# MCU.net
KiCad netlist of a schematic drawn in Altium Designer
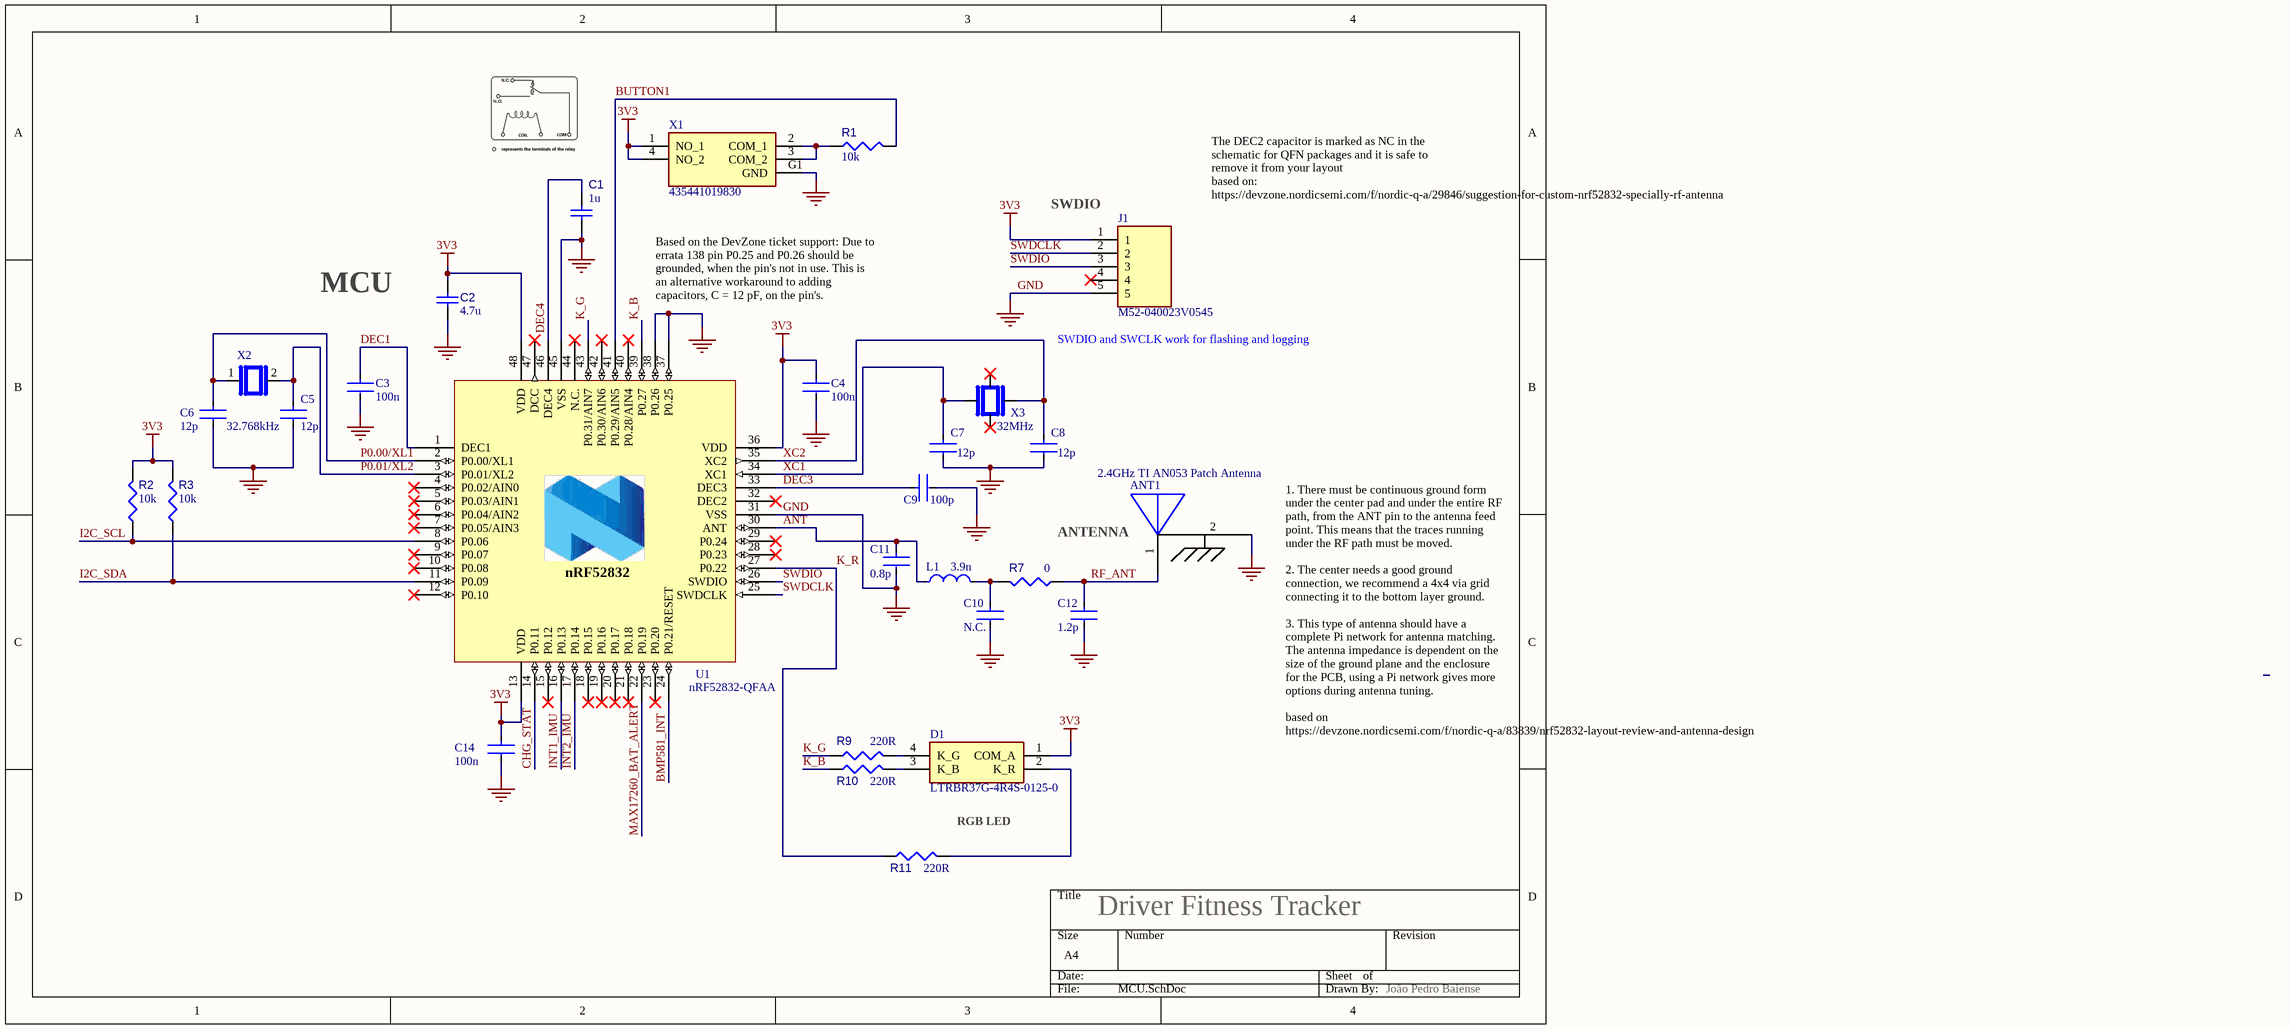
[diagram p0: MCU.SchDoc]

(export (version "E")
  (design (tool "Eeschema 10.0.6"))
  (components
    (comp (ref "ANT1")
      (value "2.4GHz TI AN053 Patch Antenna")
      (footprint "2.4GHz TI AN053 Patch Antenna Right Original")
      (description "From Application Note AN053")
      (libsource (lib "Tese_SymbolLib") (part "2.4GHz Antenna with GND"))
    )
    (comp (ref "C1")
      (value "1u")
      (footprint "CAPC1608X90X40NL10T20")
      (description "Multilayer Ceramic Capacitors MLCC - SMD/SMT 50V 1uF X7R 0603 10%")
      (fields (field (name "TOLERANCE") "10%") (field (name "JLCPCB PART #") "C15849"))
      (libsource (lib "Tese_project") (part "CAP-NP-2"))
    )
    (comp (ref "C2")
      (value "4.7u")
      (footprint "CAPC1608X90X40NL10T20")
      (description "Chip Capacitor, 100 nF, +/- 10%, 50 V, 0603 (1608 Metric)")
      (fields (field (name "TOLERANCE") "10%") (field (name "JLCPCB PART #") "C14663"))
      (libsource (lib "Tese_project") (part "CAP-NP-2"))
    )
    (comp (ref "C3")
      (value "100n")
      (footprint "FP-C0402-BB-MFG")
      (description "Multilayer Ceramic Capacitors MLCC - SMD/SMT NEW GLOBAL PN KGM05CR71H104KN 50V 0.1uF X7R 0402 10%")
      (fields (field (name "MANUFACTURER") "Kemet") (field (name "TOLERANCE") "0.1"))
      (libsource (lib "Altium Content Vault") (part "b4654b650e69147ec39a6b967a45e02"))
    )
    (comp (ref "C4")
      (value "100n")
      (footprint "FP-C0402-BB-MFG")
      (description "Multilayer Ceramic Capacitors MLCC - SMD/SMT NEW GLOBAL PN KGM05CR71H104KN 50V 0.1uF X7R 0402 10%")
      (fields (field (name "MANUFACTURER") "Kemet") (field (name "TOLERANCE") "0.1"))
      (libsource (lib "Altium Content Vault") (part "b4654b650e69147ec39a6b967a45e02"))
    )
    (comp (ref "C5")
      (value "12p")
      (footprint "FP-C0402-BB-MFG")
      (description "Multilayer Ceramic Capacitors MLCC - SMD/SMT 12 pF 50 VDC 5% 0402 C0G (NP0)")
      (fields (field (name "MANUFACTURER") "Kemet") (field (name "TOLERANCE") "0.1"))
      (libsource (lib "Altium Content Vault") (part "b4654b650e69147ec39a6b967a45e02"))
    )
    (comp (ref "C6")
      (value "12p")
      (footprint "FP-C0402-BB-MFG")
      (description "Multilayer Ceramic Capacitors MLCC - SMD/SMT 12 pF 50 VDC 5% 0402 C0G (NP0)")
      (fields (field (name "MANUFACTURER") "Kemet") (field (name "TOLERANCE") "0.1"))
      (libsource (lib "Altium Content Vault") (part "b4654b650e69147ec39a6b967a45e02"))
    )
    (comp (ref "C7")
      (value "12p")
      (footprint "FP-C0402-BB-MFG")
      (description "Multilayer Ceramic Capacitors MLCC - SMD/SMT 12 pF 50 VDC 5% 0402 C0G (NP0)")
      (fields (field (name "MANUFACTURER") "Kemet") (field (name "TOLERANCE") "0.1"))
      (libsource (lib "Altium Content Vault") (part "b4654b650e69147ec39a6b967a45e02"))
    )
    (comp (ref "C8")
      (value "12p")
      (footprint "FP-C0402-BB-MFG")
      (description "Multilayer Ceramic Capacitors MLCC - SMD/SMT 12 pF 50 VDC 5% 0402 C0G (NP0)")
      (fields (field (name "MANUFACTURER") "Kemet") (field (name "TOLERANCE") "0.1"))
      (libsource (lib "Altium Content Vault") (part "b4654b650e69147ec39a6b967a45e02"))
    )
    (comp (ref "C9")
      (value "100p")
      (footprint "FP-C0402-BB-MFG")
      (description "Multilayer Ceramic Capacitors MLCC - SMD/SMT 100 pF 50 VDC 5% 0402 C0G (NP0)")
      (fields (field (name "MANUFACTURER") "Kemet") (field (name "TOLERANCE") "0.1"))
      (libsource (lib "Altium Content Vault") (part "b4654b650e69147ec39a6b967a45e02"))
    )
    (comp (ref "C10")
      (value "N.C.")
      (footprint "FP-C0402-BB-MFG")
      (description "DO NOT CONNECT THIS CAPACITOR - RF PURPOSE")
      (libsource (lib "Altium Content Vault") (part "b4654b650e69147ec39a6b967a45e02"))
    )
    (comp (ref "C11")
      (value "0.8p")
      (footprint "FP-C0402-BB-MFG")
      (description "Multilayer Ceramic Capacitors MLCC - SMD/SMT 0.8 pF 50 VDC 0.05 pF 0402 C0G (NP0) AEC-Q200")
      (fields (field (name "MANUFACTURER") "Murata Electronics") (field (name "TOLERANCE") "0.1"))
      (libsource (lib "Altium Content Vault") (part "b4654b650e69147ec39a6b967a45e02"))
    )
    (comp (ref "C12")
      (value "1.2p")
      (footprint "FP-C0402-BB-MFG")
      (fields
        (field (name "MANUFACTURER") "Kemet")
        (field (name "TOLERANCE") "0.1")
        (field (name "OCTOPART") "https://octopart.com/c0402c104k8pactu-kemet-140039")
      )
      (libsource (lib "Altium Content Vault") (part "b4654b650e69147ec39a6b967a45e02"))
    )
    (comp (ref "C14")
      (value "100n")
      (footprint "FP-C0402-BB-MFG")
      (description "Multilayer Ceramic Capacitors MLCC - SMD/SMT NEW GLOBAL PN KGM05CR71H104KN 50V 0.1uF X7R 0402 10%")
      (fields (field (name "MANUFACTURER") "Kemet") (field (name "TOLERANCE") "0.1"))
      (libsource (lib "Altium Content Vault") (part "b4654b650e69147ec39a6b967a45e02"))
    )
    (comp (ref "D1")
      (value "LTRBR37G-4R4S-0125-0")
      (footprint "RGBLED_LTRBR37G4R4S01250")
      (description "Standard LEDs - SMD LTRBR37G")
      (fields (field (name "MOUSER PART NUMBER") "720-LTRBR37GA6714"))
      (libsource (lib "Tese_SymbolLib") (part "RGBLED_LTRBR37G-4R4S-0125-0"))
    )
    (comp (ref "J1")
      (value "M52-040023V0545")
      (footprint "5_PINS_HEADER_HDRV5W46P0X127_1X5_635X250X650P")
      (description "Headers & Wire Housings Pin1.27mm Tail,Vert SIL, 5P, Single Row")
      (fields (field (name "MOUSER PART NUMBER") "855-M52-040023V0545"))
      (libsource (lib "Tese_SymbolLib") (part "5_PINS_HEADER_M52-040023V0545"))
    )
    (comp (ref "L1")
      (value "3.9n")
      (footprint "FP-LQW15AN_00-W0_6-0_1-MFG")
      (description "RF Inductors - SMD 01005, 3.9nH +-0.2nH S-HQ SMD RF IND")
      (fields (field (name "JLCPCB PART #") "C14033"))
      (libsource (lib "Altium Content Vault") (part "725321dda6339637d4d059423bc1c3c"))
    )
    (comp (ref "R1")
      (value "10k")
      (footprint "RESC0402(1005)_L")
      (description "Thin Film Resistors - SMD 1/16W 10K ohm 1% 50ppm")
      (fields (field (name "POWER") "63mW") (field (name "TOLERANCE") "1%"))
      (libsource (lib "Tese_project") (part "RES-2"))
    )
    (comp (ref "R2")
      (value "10k")
      (footprint "RESC0402(1005)_L")
      (description "Thin Film Resistors - SMD 1/16W 10K ohm 1% 50ppm")
      (fields (field (name "POWER") "63mW") (field (name "TOLERANCE") "1%"))
      (libsource (lib "Tese_project") (part "RES-2"))
    )
    (comp (ref "R3")
      (value "10k")
      (footprint "RESC0402(1005)_L")
      (description "Thin Film Resistors - SMD 1/16W 10K ohm 1% 50ppm")
      (fields (field (name "POWER") "63mW") (field (name "TOLERANCE") "1%"))
      (libsource (lib "Tese_project") (part "RES-2"))
    )
    (comp (ref "R7")
      (value "0")
      (footprint "RESC0402(1005)_L")
      (description "Thin Film Resistors - SMD MCS 0402 VG01 E1 0R0")
      (fields (field (name "POWER") "63mW") (field (name "TOLERANCE") "1%"))
      (libsource (lib "Tese_project") (part "RES-2"))
    )
    (comp (ref "R9")
      (value "220R")
      (footprint "RESC0402(1005)_L")
      (description "Thin Film Resistors - SMD .063W 220ohms 1% 0402 50ppm")
      (fields (field (name "POWER") "63mW") (field (name "TOLERANCE") "1%"))
      (libsource (lib "Tese_project") (part "RES-2"))
    )
    (comp (ref "R10")
      (value "220R")
      (footprint "RESC0402(1005)_L")
      (description "Thin Film Resistors - SMD .063W 220ohms 1% 0402 50ppm")
      (fields (field (name "POWER") "63mW") (field (name "TOLERANCE") "1%"))
      (libsource (lib "Tese_project") (part "RES-2"))
    )
    (comp (ref "R11")
      (value "220R")
      (footprint "RESC0402(1005)_L")
      (description "Thin Film Resistors - SMD .063W 220ohms 1% 0402 50ppm")
      (fields (field (name "POWER") "63mW") (field (name "TOLERANCE") "1%"))
      (libsource (lib "Tese_project") (part "RES-2"))
    )
    (comp (ref "U1")
      (value "nRF52832-QFAA")
      (footprint "QFN40P600X600X90-48N")
      (description "Multi-protocol Bluetooth Low Energy, ANT and 2.4GHz proprietary system-on-chip")
      (fields
        (field (name "MANUFACTURER") "Nordic Semiconductor")
        (field (name "JLCPCB PART #") "C77540")
        (field (name "PUBLISHER") "Nordic Semiconductor")
      )
      (libsource (lib "Tese_SymbolLib") (part "nRF52832_QFAA"))
    )
    (comp (ref "X1")
      (value "435441019830")
      (footprint "BUTTON_435441019830")
      (description "Tactile Switches WS-TASV Tact Switch Washable 4.1x2.8x1.9 mm SMT")
      (fields (field (name "MOUSER PART NUMBER") "710-435441019830"))
      (libsource (lib "Tese_SymbolLib") (part "BUTTON_435441019830"))
    )
    (comp (ref "X2")
      (value "32.768kHz")
      (footprint "CRYSTAL_XTAL_CM8V-T1A-32.768KHZ-9PF-20PPM-TA-QC")
      (description "Crystals 32.768 kHz 9.0 pF +/-20 PPM -40/+85C")
      (fields (field (name "MF") "Micro Crystal"))
      (libsource (lib "Tese_SymbolLib") (part "CRYSTAL_32K"))
    )
    (comp (ref "X3")
      (value "32MHz")
      (footprint "OSC_XRCGB32M000F1H01R0")
      (description "Crystals 32 MHZ 10PPM 2.0X1.6X")
      (fields (field (name "MF") "Murata Electronics") (field (name "JLCPCB PART #") "C914155"))
      (libsource (lib "Tese_SymbolLib") (part "XRCGB32M000F1H01R0"))
    )
  )
  (nets
    (net (code "1") (name "/ANT") (class "Default")
      (node (ref "C11") (pin "1") (pinfunction "1_1") (pintype "passive"))
      (node (ref "L1") (pin "1") (pinfunction "1_1") (pintype "passive"))
      (node (ref "U1") (pin "30") (pinfunction "ANT_30") (pintype "bidirectional"))
    )
    (net (code "2") (name "/BMP581_INT") (class "Default")
      (node (ref "U1") (pin "24") (pinfunction "P0.21/RESET_24") (pintype "bidirectional"))
    )
    (net (code "3") (name "/BUTTON1") (class "Default")
      (node (ref "R1") (pin "2") (pinfunction "2_2") (pintype "passive"))
      (node (ref "U1") (pin "41") (pinfunction "P0.29/AIN5_41") (pintype "bidirectional"))
    )
    (net (code "4") (name "/CHG_STAT") (class "Default")
      (node (ref "U1") (pin "14") (pinfunction "P0.11_14") (pintype "bidirectional"))
    )
    (net (code "5") (name "/DEC1") (class "Default")
      (node (ref "C3") (pin "1") (pinfunction "1_1") (pintype "passive"))
      (node (ref "U1") (pin "1") (pinfunction "DEC1_1") (pintype "power_in"))
    )
    (net (code "6") (name "/DEC3") (class "Default")
      (node (ref "C9") (pin "1") (pinfunction "1_1") (pintype "passive"))
      (node (ref "U1") (pin "33") (pinfunction "DEC3_33") (pintype "power_in"))
    )
    (net (code "7") (name "/DEC4") (class "Default")
      (node (ref "C1") (pin "1") (pinfunction "1_1") (pintype "passive"))
      (node (ref "U1") (pin "46") (pinfunction "DEC4_46") (pintype "power_in"))
    )
    (net (code "8") (name "/I2C_SCL") (class "Default")
      (node (ref "R2") (pin "1") (pinfunction "1_1") (pintype "passive"))
      (node (ref "U1") (pin "8") (pinfunction "P0.06_8") (pintype "bidirectional"))
    )
    (net (code "9") (name "/I2C_SDA") (class "Default")
      (node (ref "R3") (pin "1") (pinfunction "1_1") (pintype "passive"))
      (node (ref "U1") (pin "11") (pinfunction "P0.09_11") (pintype "bidirectional"))
    )
    (net (code "10") (name "/INT1_IMU") (class "Default")
      (node (ref "U1") (pin "16") (pinfunction "P0.13_16") (pintype "bidirectional"))
    )
    (net (code "11") (name "/INT2_IMU") (class "Default")
      (node (ref "U1") (pin "17") (pinfunction "P0.14_17") (pintype "bidirectional"))
    )
    (net (code "12") (name "/K_B") (class "Default")
      (node (ref "R10") (pin "1") (pinfunction "1_1") (pintype "passive"))
      (node (ref "U1") (pin "39") (pinfunction "P0.27_39") (pintype "bidirectional"))
    )
    (net (code "13") (name "/K_G") (class "Default")
      (node (ref "R9") (pin "1") (pinfunction "1_1") (pintype "passive"))
      (node (ref "U1") (pin "43") (pinfunction "P0.31/AIN7_43") (pintype "bidirectional"))
    )
    (net (code "14") (name "/K_R") (class "Default")
      (node (ref "R11") (pin "1") (pinfunction "1_1") (pintype "passive"))
      (node (ref "U1") (pin "27") (pinfunction "P0.22_27") (pintype "bidirectional"))
    )
    (net (code "15") (name "/MAX17260_BAT_ALERT") (class "Default")
      (node (ref "U1") (pin "22") (pinfunction "P0.19_22") (pintype "bidirectional"))
    )
    (net (code "16") (name "/P0.00{slash}XL1") (class "Default")
      (node (ref "C6") (pin "1") (pinfunction "1_1") (pintype "passive"))
      (node (ref "U1") (pin "2") (pinfunction "P0.00/XL1_2") (pintype "bidirectional"))
      (node (ref "X2") (pin "1") (pinfunction "1_1") (pintype "passive"))
    )
    (net (code "17") (name "/P0.01{slash}XL2") (class "Default")
      (node (ref "C5") (pin "1") (pinfunction "1_1") (pintype "passive"))
      (node (ref "U1") (pin "3") (pinfunction "P0.01/XL2_3") (pintype "bidirectional"))
      (node (ref "X2") (pin "2") (pinfunction "2_2") (pintype "passive"))
    )
    (net (code "18") (name "/RF_ANT") (class "Default")
      (node (ref "ANT1") (pin "1") (pinfunction "ANT_1") (pintype "passive"))
      (node (ref "C12") (pin "1") (pinfunction "1_1") (pintype "passive"))
      (node (ref "R7") (pin "1") (pinfunction "1_1") (pintype "passive"))
    )
    (net (code "19") (name "/SWDCLK") (class "Default")
      (node (ref "J1") (pin "2") (pinfunction "2_2") (pintype "passive"))
      (node (ref "U1") (pin "25") (pinfunction "SWDCLK_25") (pintype "input"))
    )
    (net (code "20") (name "/SWDIO") (class "Default")
      (node (ref "J1") (pin "3") (pinfunction "3_3") (pintype "passive"))
      (node (ref "U1") (pin "26") (pinfunction "SWDIO_26") (pintype "bidirectional"))
    )
    (net (code "21") (name "/XC1") (class "Default")
      (node (ref "C7") (pin "1") (pinfunction "1_1") (pintype "passive"))
      (node (ref "U1") (pin "34") (pinfunction "XC1_34") (pintype "input"))
      (node (ref "X3") (pin "1") (pinfunction "1_1") (pintype "passive"))
    )
    (net (code "22") (name "/XC2") (class "Default")
      (node (ref "C8") (pin "1") (pinfunction "1_1") (pintype "passive"))
      (node (ref "U1") (pin "35") (pinfunction "XC2_35") (pintype "output"))
      (node (ref "X3") (pin "3") (pinfunction "3_3") (pintype "passive"))
    )
    (net (code "23") (name "3V3") (class "Default")
      (node (ref "C14") (pin "1") (pinfunction "1_1") (pintype "passive"))
      (node (ref "C2") (pin "1") (pinfunction "1_1") (pintype "passive"))
      (node (ref "C4") (pin "1") (pinfunction "1_1") (pintype "passive"))
      (node (ref "D1") (pin "1") (pinfunction "COM_A_1") (pintype "passive"))
      (node (ref "J1") (pin "1") (pinfunction "1_1") (pintype "passive"))
      (node (ref "R2") (pin "2") (pinfunction "2_2") (pintype "passive"))
      (node (ref "R3") (pin "2") (pinfunction "2_2") (pintype "passive"))
      (node (ref "U1") (pin "13") (pinfunction "VDD_13") (pintype "power_in"))
      (node (ref "U1") (pin "36") (pinfunction "VDD_36") (pintype "power_in"))
      (node (ref "U1") (pin "48") (pinfunction "VDD_48") (pintype "power_in"))
      (node (ref "X1") (pin "1") (pinfunction "NO_1_1") (pintype "passive"))
      (node (ref "X1") (pin "4") (pinfunction "NO_2_4") (pintype "passive"))
    )
    (net (code "24") (name "GND") (class "Default")
      (node (ref "ANT1") (pin "2") (pintype "passive"))
      (node (ref "C1") (pin "2") (pinfunction "2_2") (pintype "passive"))
      (node (ref "C10") (pin "2") (pinfunction "2_2") (pintype "passive"))
      (node (ref "C11") (pin "2") (pinfunction "2_2") (pintype "passive"))
      (node (ref "C12") (pin "2") (pinfunction "2_2") (pintype "passive"))
      (node (ref "C14") (pin "2") (pinfunction "2_2") (pintype "passive"))
      (node (ref "C2") (pin "2") (pinfunction "2_2") (pintype "passive"))
      (node (ref "C3") (pin "2") (pinfunction "2_2") (pintype "passive"))
      (node (ref "C4") (pin "2") (pinfunction "2_2") (pintype "passive"))
      (node (ref "C5") (pin "2") (pinfunction "2_2") (pintype "passive"))
      (node (ref "C6") (pin "2") (pinfunction "2_2") (pintype "passive"))
      (node (ref "C7") (pin "2") (pinfunction "2_2") (pintype "passive"))
      (node (ref "C8") (pin "2") (pinfunction "2_2") (pintype "passive"))
      (node (ref "C9") (pin "2") (pinfunction "2_2") (pintype "passive"))
      (node (ref "J1") (pin "5") (pinfunction "5_5") (pintype "passive"))
      (node (ref "U1") (pin "31") (pinfunction "VSS_31") (pintype "power_in"))
      (node (ref "U1") (pin "37") (pinfunction "P0.25_37") (pintype "bidirectional"))
      (node (ref "U1") (pin "38") (pinfunction "P0.26_38") (pintype "bidirectional"))
      (node (ref "U1") (pin "45") (pinfunction "VSS_45") (pintype "power_in"))
      (node (ref "U1") (pin "49") (pinfunction "GND_49") (pintype "power_in"))
      (node (ref "X1") (pin "G1") (pinfunction "GND_G1") (pintype "passive"))
    )
    (net (code "25") (name "Net-(C10-Pad1)") (class "Default")
      (node (ref "C10") (pin "1") (pinfunction "1_1") (pintype "passive"))
      (node (ref "L1") (pin "2") (pinfunction "2_2") (pintype "passive"))
      (node (ref "R7") (pin "2") (pinfunction "2_2") (pintype "passive"))
    )
    (net (code "26") (name "Net-(D1-K_B)") (class "Default")
      (node (ref "D1") (pin "3") (pinfunction "K_B_3") (pintype "passive"))
      (node (ref "R10") (pin "2") (pinfunction "2_2") (pintype "passive"))
    )
    (net (code "27") (name "Net-(D1-K_G)") (class "Default")
      (node (ref "D1") (pin "4") (pinfunction "K_G_4") (pintype "passive"))
      (node (ref "R9") (pin "2") (pinfunction "2_2") (pintype "passive"))
    )
    (net (code "28") (name "Net-(D1-K_R)") (class "Default")
      (node (ref "D1") (pin "2") (pinfunction "K_R_2") (pintype "passive"))
      (node (ref "R11") (pin "2") (pinfunction "2_2") (pintype "passive"))
    )
    (net (code "29") (name "Net-(X1-COM_1)") (class "Default")
      (node (ref "R1") (pin "1") (pinfunction "1_1") (pintype "passive"))
      (node (ref "X1") (pin "2") (pinfunction "COM_1_2") (pintype "passive"))
      (node (ref "X1") (pin "3") (pinfunction "COM_2_3") (pintype "passive"))
    )
    (net (code "30") (name "unconnected-(J1-Pad4)") (class "Default")
      (node (ref "J1") (pin "4") (pinfunction "4_4") (pintype "passive+no_connect"))
    )
    (net (code "31") (name "unconnected-(U1-DCC-Pad47)") (class "Default")
      (node (ref "U1") (pin "47") (pinfunction "DCC_47") (pintype "output+no_connect"))
    )
    (net (code "32") (name "unconnected-(U1-DEC2-Pad32)") (class "Default")
      (node (ref "U1") (pin "32") (pinfunction "DEC2_32") (pintype "power_in+no_connect"))
    )
    (net (code "33") (name "unconnected-(U1-N.C.-Pad44)") (class "Default")
      (node (ref "U1") (pin "44") (pinfunction "N.C._44") (pintype "power_in+no_connect"))
    )
    (net (code "34") (name "unconnected-(U1-P0.02{slash}AIN0-Pad4)") (class "Default")
      (node (ref "U1") (pin "4") (pinfunction "P0.02/AIN0_4") (pintype "bidirectional+no_connect"))
    )
    (net (code "35") (name "unconnected-(U1-P0.03{slash}AIN1-Pad5)") (class "Default")
      (node (ref "U1") (pin "5") (pinfunction "P0.03/AIN1_5") (pintype "bidirectional+no_connect"))
    )
    (net (code "36") (name "unconnected-(U1-P0.04{slash}AIN2-Pad6)") (class "Default")
      (node (ref "U1") (pin "6") (pinfunction "P0.04/AIN2_6") (pintype "bidirectional+no_connect"))
    )
    (net (code "37") (name "unconnected-(U1-P0.05{slash}AIN3-Pad7)") (class "Default")
      (node (ref "U1") (pin "7") (pinfunction "P0.05/AIN3_7") (pintype "bidirectional+no_connect"))
    )
    (net (code "38") (name "unconnected-(U1-P0.07-Pad9)") (class "Default")
      (node (ref "U1") (pin "9") (pinfunction "P0.07_9") (pintype "bidirectional+no_connect"))
    )
    (net (code "39") (name "unconnected-(U1-P0.08-Pad10)") (class "Default")
      (node (ref "U1") (pin "10") (pinfunction "P0.08_10") (pintype "bidirectional+no_connect"))
    )
    (net (code "40") (name "unconnected-(U1-P0.10-Pad12)") (class "Default")
      (node (ref "U1") (pin "12") (pinfunction "P0.10_12") (pintype "bidirectional+no_connect"))
    )
    (net (code "41") (name "unconnected-(U1-P0.12-Pad15)") (class "Default")
      (node (ref "U1") (pin "15") (pinfunction "P0.12_15") (pintype "bidirectional+no_connect"))
    )
    (net (code "42") (name "unconnected-(U1-P0.15-Pad18)") (class "Default")
      (node (ref "U1") (pin "18") (pinfunction "P0.15_18") (pintype "bidirectional+no_connect"))
    )
    (net (code "43") (name "unconnected-(U1-P0.16-Pad19)") (class "Default")
      (node (ref "U1") (pin "19") (pinfunction "P0.16_19") (pintype "bidirectional+no_connect"))
    )
    (net (code "44") (name "unconnected-(U1-P0.17-Pad20)") (class "Default")
      (node (ref "U1") (pin "20") (pinfunction "P0.17_20") (pintype "bidirectional+no_connect"))
    )
    (net (code "45") (name "unconnected-(U1-P0.18-Pad21)") (class "Default")
      (node (ref "U1") (pin "21") (pinfunction "P0.18_21") (pintype "bidirectional+no_connect"))
    )
    (net (code "46") (name "unconnected-(U1-P0.20-Pad23)") (class "Default")
      (node (ref "U1") (pin "23") (pinfunction "P0.20_23") (pintype "bidirectional+no_connect"))
    )
    (net (code "47") (name "unconnected-(U1-P0.23-Pad28)") (class "Default")
      (node (ref "U1") (pin "28") (pinfunction "P0.23_28") (pintype "bidirectional+no_connect"))
    )
    (net (code "48") (name "unconnected-(U1-P0.24-Pad29)") (class "Default")
      (node (ref "U1") (pin "29") (pinfunction "P0.24_29") (pintype "bidirectional+no_connect"))
    )
    (net (code "49") (name "unconnected-(U1-P0.28{slash}AIN4-Pad40)") (class "Default")
      (node (ref "U1") (pin "40") (pinfunction "P0.28/AIN4_40") (pintype "bidirectional+no_connect"))
    )
    (net (code "50") (name "unconnected-(U1-P0.30{slash}AIN6-Pad42)") (class "Default")
      (node (ref "U1") (pin "42") (pinfunction "P0.30/AIN6_42") (pintype "bidirectional+no_connect"))
    )
    (net (code "51") (name "unconnected-(X3-Pad2)") (class "Default")
      (node (ref "X3") (pin "2") (pinfunction "2_2") (pintype "power_in+no_connect"))
    )
    (net (code "52") (name "unconnected-(X3-Pad4)") (class "Default")
      (node (ref "X3") (pin "4") (pinfunction "4_4") (pintype "power_in+no_connect"))
    )
  )
)
